# DRIVERS.net
KiCad netlist of a schematic drawn in Altium Designer
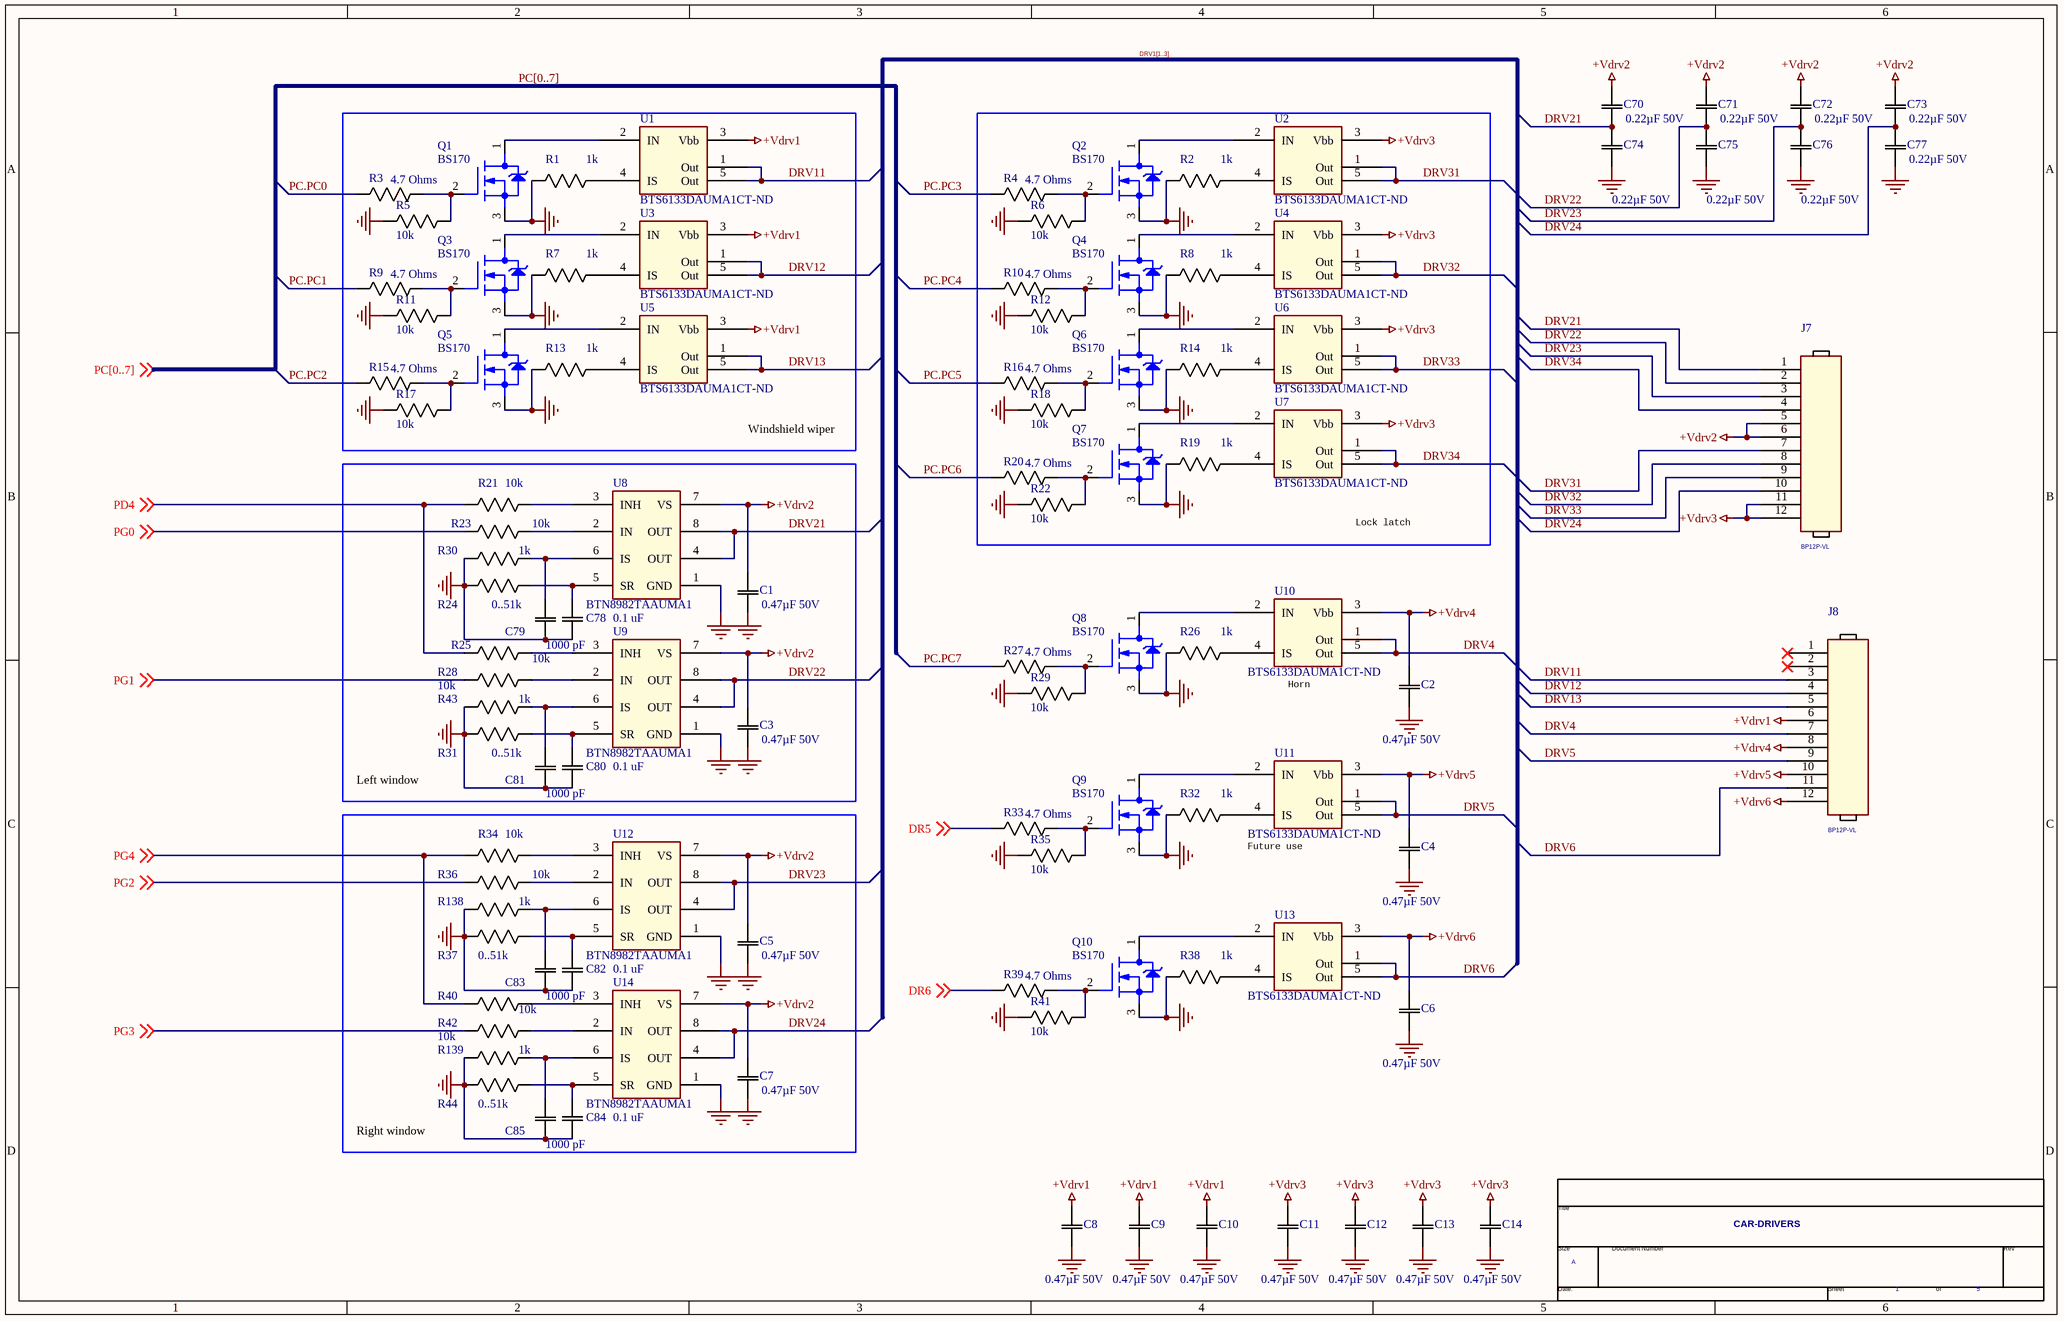
[diagram p0: DRIVERS.SchDoc]

(export (version "E")
  (design (tool "Eeschema 10.0.6"))
  (components
    (comp (ref "C1")
      (value "0.47µF 50V")
      (footprint "SR20")
      (description "CAP CER 0.47UF 50V X7R RADIAL")
      (fields (field (name "MANUFACTURER_PART_NUMBER") "C315C474K5R5TA7303"))
      (libsource (lib "Discrete") (part "CAP RADIAL 2.54"))
    )
    (comp (ref "C2")
      (value "0.47µF 50V")
      (footprint "SR20")
      (description "CAP CER 0.47UF 50V X7R RADIAL")
      (fields (field (name "MANUFACTURER_PART_NUMBER") "C315C474K5R5TA7303"))
      (libsource (lib "Discrete") (part "CAP RADIAL 2.54"))
    )
    (comp (ref "C3")
      (value "0.47µF 50V")
      (footprint "SR20")
      (description "CAP CER 0.47UF 50V X7R RADIAL")
      (fields (field (name "MANUFACTURER_PART_NUMBER") "C315C474K5R5TA7303"))
      (libsource (lib "Discrete") (part "CAP RADIAL 2.54"))
    )
    (comp (ref "C4")
      (value "0.47µF 50V")
      (footprint "SR20")
      (description "CAP CER 0.47UF 50V X7R RADIAL")
      (fields (field (name "MANUFACTURER_PART_NUMBER") "C315C474K5R5TA7303"))
      (libsource (lib "Discrete") (part "CAP RADIAL 2.54"))
    )
    (comp (ref "C5")
      (value "0.47µF 50V")
      (footprint "SR20")
      (description "CAP CER 0.47UF 50V X7R RADIAL")
      (fields (field (name "MANUFACTURER_PART_NUMBER") "C315C474K5R5TA7303"))
      (libsource (lib "Discrete") (part "CAP RADIAL 2.54"))
    )
    (comp (ref "C6")
      (value "0.47µF 50V")
      (footprint "SR20")
      (description "CAP CER 0.47UF 50V X7R RADIAL")
      (fields (field (name "MANUFACTURER_PART_NUMBER") "C315C474K5R5TA7303"))
      (libsource (lib "Discrete") (part "CAP RADIAL 2.54"))
    )
    (comp (ref "C7")
      (value "0.47µF 50V")
      (footprint "SR20")
      (description "CAP CER 0.47UF 50V X7R RADIAL")
      (fields (field (name "MANUFACTURER_PART_NUMBER") "C315C474K5R5TA7303"))
      (libsource (lib "Discrete") (part "CAP RADIAL 2.54"))
    )
    (comp (ref "C8")
      (value "0.47µF 50V")
      (footprint "SR20")
      (description "CAP CER 0.47UF 50V X7R RADIAL")
      (fields (field (name "MANUFACTURER_PART_NUMBER") "C315C474K5R5TA7303"))
      (libsource (lib "Discrete") (part "CAP RADIAL 2.54"))
    )
    (comp (ref "C9")
      (value "0.47µF 50V")
      (footprint "SR20")
      (description "CAP CER 0.47UF 50V X7R RADIAL")
      (fields (field (name "MANUFACTURER_PART_NUMBER") "C315C474K5R5TA7303"))
      (libsource (lib "Discrete") (part "CAP RADIAL 2.54"))
    )
    (comp (ref "C10")
      (value "0.47µF 50V")
      (footprint "SR20")
      (description "CAP CER 0.47UF 50V X7R RADIAL")
      (fields (field (name "MANUFACTURER_PART_NUMBER") "C315C474K5R5TA7303"))
      (libsource (lib "Discrete") (part "CAP RADIAL 2.54"))
    )
    (comp (ref "C11")
      (value "0.47µF 50V")
      (footprint "SR20")
      (description "CAP CER 0.47UF 50V X7R RADIAL")
      (fields (field (name "MANUFACTURER_PART_NUMBER") "C315C474K5R5TA7303"))
      (libsource (lib "Discrete") (part "CAP RADIAL 2.54"))
    )
    (comp (ref "C12")
      (value "0.47µF 50V")
      (footprint "SR20")
      (description "CAP CER 0.47UF 50V X7R RADIAL")
      (fields (field (name "MANUFACTURER_PART_NUMBER") "C315C474K5R5TA7303"))
      (libsource (lib "Discrete") (part "CAP RADIAL 2.54"))
    )
    (comp (ref "C13")
      (value "0.47µF 50V")
      (footprint "SR20")
      (description "CAP CER 0.47UF 50V X7R RADIAL")
      (fields (field (name "MANUFACTURER_PART_NUMBER") "C315C474K5R5TA7303"))
      (libsource (lib "Discrete") (part "CAP RADIAL 2.54"))
    )
    (comp (ref "C14")
      (value "0.47µF 50V")
      (footprint "SR20")
      (description "CAP CER 0.47UF 50V X7R RADIAL")
      (fields (field (name "MANUFACTURER_PART_NUMBER") "C315C474K5R5TA7303"))
      (libsource (lib "Discrete") (part "CAP RADIAL 2.54"))
    )
    (comp (ref "C70")
      (value "0.22µF 50V")
      (footprint "SR20")
      (description "CAP CER 0.22UF 50V X7R RADIAL")
      (fields (field (name "MANUFACTURER_PART_NUMBER") "C320C224K5R5TA"))
      (libsource (lib "Discrete") (part "CAP RADIAL 2.54"))
    )
    (comp (ref "C71")
      (value "0.22µF 50V")
      (footprint "SR20")
      (description "CAP CER 0.22UF 50V X7R RADIAL")
      (fields (field (name "MANUFACTURER_PART_NUMBER") "C320C224K5R5TA"))
      (libsource (lib "Discrete") (part "CAP RADIAL 2.54"))
    )
    (comp (ref "C72")
      (value "0.22µF 50V")
      (footprint "SR20")
      (description "CAP CER 0.22UF 50V X7R RADIAL")
      (fields (field (name "MANUFACTURER_PART_NUMBER") "C320C224K5R5TA"))
      (libsource (lib "Discrete") (part "CAP RADIAL 2.54"))
    )
    (comp (ref "C73")
      (value "0.22µF 50V")
      (footprint "SR20")
      (description "CAP CER 0.22UF 50V X7R RADIAL")
      (fields (field (name "MANUFACTURER_PART_NUMBER") "C320C224K5R5TA"))
      (libsource (lib "Discrete") (part "CAP RADIAL 2.54"))
    )
    (comp (ref "C74")
      (value "0.22µF 50V")
      (footprint "SR20")
      (description "CAP CER 0.22UF 50V X7R RADIAL")
      (fields (field (name "MANUFACTURER_PART_NUMBER") "C320C224K5R5TA"))
      (libsource (lib "Discrete") (part "CAP RADIAL 2.54"))
    )
    (comp (ref "C75")
      (value "0.22µF 50V")
      (footprint "SR20")
      (description "CAP CER 0.22UF 50V X7R RADIAL")
      (fields (field (name "MANUFACTURER_PART_NUMBER") "C320C224K5R5TA"))
      (libsource (lib "Discrete") (part "CAP RADIAL 2.54"))
    )
    (comp (ref "C76")
      (value "0.22µF 50V")
      (footprint "SR20")
      (description "CAP CER 0.22UF 50V X7R RADIAL")
      (fields (field (name "MANUFACTURER_PART_NUMBER") "C320C224K5R5TA"))
      (libsource (lib "Discrete") (part "CAP RADIAL 2.54"))
    )
    (comp (ref "C77")
      (value "0.22µF 50V")
      (footprint "SR20")
      (description "CAP CER 0.22UF 50V X7R RADIAL")
      (fields (field (name "MANUFACTURER_PART_NUMBER") "C320C224K5R5TA"))
      (libsource (lib "Discrete") (part "CAP RADIAL 2.54"))
    )
    (comp (ref "C78")
      (value "0.1 uF")
      (footprint "SR20")
      (description "0.1µF ±10% 100V Ceramic Capacitor X7R Radial")
      (fields (field (name "MANUFACTURER_PART_NUMBER") "C320C104K1R5TA7301"))
      (libsource (lib "Discrete") (part "CAP RADIAL 2.54"))
    )
    (comp (ref "C79")
      (value "1000 pF")
      (footprint "SR20")
      (description "CAP CER 1000PF 50V X7R RADIAL")
      (fields (field (name "MANUFACTURER_PART_NUMBER") "C315C102K5R5TA7301"))
      (libsource (lib "Discrete") (part "CAP RADIAL 2.54"))
    )
    (comp (ref "C80")
      (value "0.1 uF")
      (footprint "SR20")
      (description "0.1µF ±10% 100V Ceramic Capacitor X7R Radial")
      (fields (field (name "MANUFACTURER_PART_NUMBER") "C320C104K1R5TA7301"))
      (libsource (lib "Discrete") (part "CAP RADIAL 2.54"))
    )
    (comp (ref "C81")
      (value "1000 pF")
      (footprint "SR20")
      (description "CAP CER 1000PF 50V X7R RADIAL")
      (fields (field (name "MANUFACTURER_PART_NUMBER") "C315C102K5R5TA7301"))
      (libsource (lib "Discrete") (part "CAP RADIAL 2.54"))
    )
    (comp (ref "C82")
      (value "0.1 uF")
      (footprint "SR20")
      (description "0.1µF ±10% 100V Ceramic Capacitor X7R Radial")
      (fields (field (name "MANUFACTURER_PART_NUMBER") "C320C104K1R5TA7301"))
      (libsource (lib "Discrete") (part "CAP RADIAL 2.54"))
    )
    (comp (ref "C83")
      (value "1000 pF")
      (footprint "SR20")
      (description "CAP CER 1000PF 50V X7R RADIAL")
      (fields (field (name "MANUFACTURER_PART_NUMBER") "C315C102K5R5TA7301"))
      (libsource (lib "Discrete") (part "CAP RADIAL 2.54"))
    )
    (comp (ref "C84")
      (value "0.1 uF")
      (footprint "SR20")
      (description "0.1µF ±10% 100V Ceramic Capacitor X7R Radial")
      (fields (field (name "MANUFACTURER_PART_NUMBER") "C320C104K1R5TA7301"))
      (libsource (lib "Discrete") (part "CAP RADIAL 2.54"))
    )
    (comp (ref "C85")
      (value "1000 pF")
      (footprint "SR20")
      (description "CAP CER 1000PF 50V X7R RADIAL")
      (fields (field (name "MANUFACTURER_PART_NUMBER") "C315C102K5R5TA7301"))
      (libsource (lib "Discrete") (part "CAP RADIAL 2.54"))
    )
    (comp (ref "J7")
      (value "BP12P-VL")
      (footprint "MOLEX_0874271202")
      (libsource (lib "*") (part "HEADER 12"))
    )
    (comp (ref "J8")
      (value "BP12P-VL")
      (footprint "MOLEX_0874271202")
      (libsource (lib "*") (part "HEADER 12"))
    )
    (comp (ref "Q1")
      (value "BS170")
      (footprint "Discrete:TO-92")
      (description "MOSFET N-CH 60V 500MA TO-92")
      (fields (field (name "MANUFACTURER_PART_NUMBER") "ON Semiconductor"))
      (libsource (lib "Discrete") (part "BS170"))
    )
    (comp (ref "Q2")
      (value "BS170")
      (footprint "Discrete:TO-92")
      (description "MOSFET N-CH 60V 500MA TO-92")
      (fields (field (name "MANUFACTURER_PART_NUMBER") "ON Semiconductor"))
      (libsource (lib "Discrete") (part "BS170"))
    )
    (comp (ref "Q3")
      (value "BS170")
      (footprint "Discrete:TO-92")
      (description "MOSFET N-CH 60V 500MA TO-92")
      (fields (field (name "MANUFACTURER_PART_NUMBER") "ON Semiconductor"))
      (libsource (lib "Discrete") (part "BS170"))
    )
    (comp (ref "Q4")
      (value "BS170")
      (footprint "Discrete:TO-92")
      (description "MOSFET N-CH 60V 500MA TO-92")
      (fields (field (name "MANUFACTURER_PART_NUMBER") "ON Semiconductor"))
      (libsource (lib "Discrete") (part "BS170"))
    )
    (comp (ref "Q5")
      (value "BS170")
      (footprint "Discrete:TO-92")
      (description "MOSFET N-CH 60V 500MA TO-92")
      (fields (field (name "MANUFACTURER_PART_NUMBER") "ON Semiconductor"))
      (libsource (lib "Discrete") (part "BS170"))
    )
    (comp (ref "Q6")
      (value "BS170")
      (footprint "Discrete:TO-92")
      (description "MOSFET N-CH 60V 500MA TO-92")
      (fields (field (name "MANUFACTURER_PART_NUMBER") "ON Semiconductor"))
      (libsource (lib "Discrete") (part "BS170"))
    )
    (comp (ref "Q7")
      (value "BS170")
      (footprint "Discrete:TO-92")
      (description "MOSFET N-CH 60V 500MA TO-92")
      (fields (field (name "MANUFACTURER_PART_NUMBER") "ON Semiconductor"))
      (libsource (lib "Discrete") (part "BS170"))
    )
    (comp (ref "Q8")
      (value "BS170")
      (footprint "Discrete:TO-92")
      (description "MOSFET N-CH 60V 500MA TO-92")
      (fields (field (name "MANUFACTURER_PART_NUMBER") "ON Semiconductor"))
      (libsource (lib "Discrete") (part "BS170"))
    )
    (comp (ref "Q9")
      (value "BS170")
      (footprint "Discrete:TO-92")
      (description "MOSFET N-CH 60V 500MA TO-92")
      (fields (field (name "MANUFACTURER_PART_NUMBER") "ON Semiconductor"))
      (libsource (lib "Discrete") (part "BS170"))
    )
    (comp (ref "Q10")
      (value "BS170")
      (footprint "Discrete:TO-92")
      (description "MOSFET N-CH 60V 500MA TO-92")
      (fields (field (name "MANUFACTURER_PART_NUMBER") "ON Semiconductor"))
      (libsource (lib "Discrete") (part "BS170"))
    )
    (comp (ref "R1")
      (value "1k")
      (footprint "RES AXIAL 1/6W")
      (description "RES 1K OHM 1/6W 5% AXIAL")
      (fields (field (name "MANUFACTURER_PART_NUMBER") "CFR-12JB-52-1K"))
      (libsource (lib "Discrete") (part "Resistor Axial  1/6W"))
    )
    (comp (ref "R2")
      (value "1k")
      (footprint "RES AXIAL 1/6W")
      (description "RES 1K OHM 1/6W 5% AXIAL")
      (fields (field (name "MANUFACTURER_PART_NUMBER") "CFR-12JB-52-1K"))
      (libsource (lib "Discrete") (part "Resistor Axial  1/6W"))
    )
    (comp (ref "R3")
      (value "4.7 Ohms")
      (footprint "RES AXIAL 1/6W")
      (description "RES 4.7 OHM 1/6W 5% AXIAL")
      (fields (field (name "MANUFACTURER_PART_NUMBER") "CFR-12JB-52-4R7"))
      (libsource (lib "Discrete") (part "Resistor Axial  1/6W"))
    )
    (comp (ref "R4")
      (value "4.7 Ohms")
      (footprint "RES AXIAL 1/6W")
      (description "RES 4.7 OHM 1/6W 5% AXIAL")
      (fields (field (name "MANUFACTURER_PART_NUMBER") "CFR-12JB-52-4R7"))
      (libsource (lib "Discrete") (part "Resistor Axial  1/6W"))
    )
    (comp (ref "R5")
      (value "10k")
      (footprint "RES AXIAL 1/6W")
      (description "RES 10K OHM 1/6W 5% AXIAL")
      (fields (field (name "MANUFACTURER_PART_NUMBER") "CFR-12JB-52-10K"))
      (libsource (lib "Discrete") (part "Resistor Axial  1/6W"))
    )
    (comp (ref "R6")
      (value "10k")
      (footprint "RES AXIAL 1/6W")
      (description "RES 10K OHM 1/6W 5% AXIAL")
      (fields (field (name "MANUFACTURER_PART_NUMBER") "CFR-12JB-52-10K"))
      (libsource (lib "Discrete") (part "Resistor Axial  1/6W"))
    )
    (comp (ref "R7")
      (value "1k")
      (footprint "RES AXIAL 1/6W")
      (description "RES 1K OHM 1/6W 5% AXIAL")
      (fields (field (name "MANUFACTURER_PART_NUMBER") "CFR-12JB-52-1K"))
      (libsource (lib "Discrete") (part "Resistor Axial  1/6W"))
    )
    (comp (ref "R8")
      (value "1k")
      (footprint "RES AXIAL 1/6W")
      (description "RES 1K OHM 1/6W 5% AXIAL")
      (fields (field (name "MANUFACTURER_PART_NUMBER") "CFR-12JB-52-1K"))
      (libsource (lib "Discrete") (part "Resistor Axial  1/6W"))
    )
    (comp (ref "R9")
      (value "4.7 Ohms")
      (footprint "RES AXIAL 1/6W")
      (description "RES 4.7 OHM 1/6W 5% AXIAL")
      (fields (field (name "MANUFACTURER_PART_NUMBER") "CFR-12JB-52-4R7"))
      (libsource (lib "Discrete") (part "Resistor Axial  1/6W"))
    )
    (comp (ref "R10")
      (value "4.7 Ohms")
      (footprint "RES AXIAL 1/6W")
      (description "RES 4.7 OHM 1/6W 5% AXIAL")
      (fields (field (name "MANUFACTURER_PART_NUMBER") "CFR-12JB-52-4R7"))
      (libsource (lib "Discrete") (part "Resistor Axial  1/6W"))
    )
    (comp (ref "R11")
      (value "10k")
      (footprint "RES AXIAL 1/6W")
      (description "RES 10K OHM 1/6W 5% AXIAL")
      (fields (field (name "MANUFACTURER_PART_NUMBER") "CFR-12JB-52-10K"))
      (libsource (lib "Discrete") (part "Resistor Axial  1/6W"))
    )
    (comp (ref "R12")
      (value "10k")
      (footprint "RES AXIAL 1/6W")
      (description "RES 10K OHM 1/6W 5% AXIAL")
      (fields (field (name "MANUFACTURER_PART_NUMBER") "CFR-12JB-52-10K"))
      (libsource (lib "Discrete") (part "Resistor Axial  1/6W"))
    )
    (comp (ref "R13")
      (value "1k")
      (footprint "RES AXIAL 1/6W")
      (description "RES 1K OHM 1/6W 5% AXIAL")
      (fields (field (name "MANUFACTURER_PART_NUMBER") "CFR-12JB-52-1K"))
      (libsource (lib "Discrete") (part "Resistor Axial  1/6W"))
    )
    (comp (ref "R14")
      (value "1k")
      (footprint "RES AXIAL 1/6W")
      (description "RES 1K OHM 1/6W 5% AXIAL")
      (fields (field (name "MANUFACTURER_PART_NUMBER") "CFR-12JB-52-1K"))
      (libsource (lib "Discrete") (part "Resistor Axial  1/6W"))
    )
    (comp (ref "R15")
      (value "4.7 Ohms")
      (footprint "RES AXIAL 1/6W")
      (description "RES 4.7 OHM 1/6W 5% AXIAL")
      (fields (field (name "MANUFACTURER_PART_NUMBER") "CFR-12JB-52-4R7"))
      (libsource (lib "Discrete") (part "Resistor Axial  1/6W"))
    )
    (comp (ref "R16")
      (value "4.7 Ohms")
      (footprint "RES AXIAL 1/6W")
      (description "RES 4.7 OHM 1/6W 5% AXIAL")
      (fields (field (name "MANUFACTURER_PART_NUMBER") "CFR-12JB-52-4R7"))
      (libsource (lib "Discrete") (part "Resistor Axial  1/6W"))
    )
    (comp (ref "R17")
      (value "10k")
      (footprint "RES AXIAL 1/6W")
      (description "RES 10K OHM 1/6W 5% AXIAL")
      (fields (field (name "MANUFACTURER_PART_NUMBER") "CFR-12JB-52-10K"))
      (libsource (lib "Discrete") (part "Resistor Axial  1/6W"))
    )
    (comp (ref "R18")
      (value "10k")
      (footprint "RES AXIAL 1/6W")
      (description "RES 10K OHM 1/6W 5% AXIAL")
      (fields (field (name "MANUFACTURER_PART_NUMBER") "CFR-12JB-52-10K"))
      (libsource (lib "Discrete") (part "Resistor Axial  1/6W"))
    )
    (comp (ref "R19")
      (value "1k")
      (footprint "RES AXIAL 1/6W")
      (description "RES 1K OHM 1/6W 5% AXIAL")
      (fields (field (name "MANUFACTURER_PART_NUMBER") "CFR-12JB-52-1K"))
      (libsource (lib "Discrete") (part "Resistor Axial  1/6W"))
    )
    (comp (ref "R20")
      (value "4.7 Ohms")
      (footprint "RES AXIAL 1/6W")
      (description "RES 4.7 OHM 1/6W 5% AXIAL")
      (fields (field (name "MANUFACTURER_PART_NUMBER") "CFR-12JB-52-4R7"))
      (libsource (lib "Discrete") (part "Resistor Axial  1/6W"))
    )
    (comp (ref "R21")
      (value "10k")
      (footprint "RES AXIAL 1/6W")
      (description "RES 10K OHM 1/6W 5% AXIAL")
      (fields (field (name "MANUFACTURER_PART_NUMBER") "CFR-12JB-52-10K"))
      (libsource (lib "Discrete") (part "Resistor Axial  1/6W"))
    )
    (comp (ref "R22")
      (value "10k")
      (footprint "RES AXIAL 1/6W")
      (description "RES 10K OHM 1/6W 5% AXIAL")
      (fields (field (name "MANUFACTURER_PART_NUMBER") "CFR-12JB-52-10K"))
      (libsource (lib "Discrete") (part "Resistor Axial  1/6W"))
    )
    (comp (ref "R23")
      (value "10k")
      (footprint "RES AXIAL 1/6W")
      (description "RES 10K OHM 1/6W 5% AXIAL")
      (fields (field (name "MANUFACTURER_PART_NUMBER") "CFR-12JB-52-10K"))
      (libsource (lib "Discrete") (part "Resistor Axial  1/6W"))
    )
    (comp (ref "R24")
      (value "0..51k")
      (footprint "RES AXIAL 1/6W")
      (description "RES 1/6W AXIAL")
      (libsource (lib "Discrete") (part "Resistor Axial  1/6W"))
    )
    (comp (ref "R25")
      (value "10k")
      (footprint "RES AXIAL 1/6W")
      (description "RES 10K OHM 1/6W 5% AXIAL")
      (fields (field (name "MANUFACTURER_PART_NUMBER") "CFR-12JB-52-10K"))
      (libsource (lib "Discrete") (part "Resistor Axial  1/6W"))
    )
    (comp (ref "R26")
      (value "1k")
      (footprint "RES AXIAL 1/6W")
      (description "RES 1K OHM 1/6W 5% AXIAL")
      (fields (field (name "MANUFACTURER_PART_NUMBER") "CFR-12JB-52-1K"))
      (libsource (lib "Discrete") (part "Resistor Axial  1/6W"))
    )
    (comp (ref "R27")
      (value "4.7 Ohms")
      (footprint "RES AXIAL 1/6W")
      (description "RES 4.7 OHM 1/6W 5% AXIAL")
      (fields (field (name "MANUFACTURER_PART_NUMBER") "CFR-12JB-52-4R7"))
      (libsource (lib "Discrete") (part "Resistor Axial  1/6W"))
    )
    (comp (ref "R28")
      (value "10k")
      (footprint "RES AXIAL 1/6W")
      (description "RES 10K OHM 1/6W 5% AXIAL")
      (fields (field (name "MANUFACTURER_PART_NUMBER") "CFR-12JB-52-10K"))
      (libsource (lib "Discrete") (part "Resistor Axial  1/6W"))
    )
    (comp (ref "R29")
      (value "10k")
      (footprint "RES AXIAL 1/6W")
      (description "RES 10K OHM 1/6W 5% AXIAL")
      (fields (field (name "MANUFACTURER_PART_NUMBER") "CFR-12JB-52-10K"))
      (libsource (lib "Discrete") (part "Resistor Axial  1/6W"))
    )
    (comp (ref "R30")
      (value "1k")
      (footprint "RES AXIAL 1/6W")
      (description "RES 1K OHM 1/6W 5% AXIAL")
      (fields (field (name "MANUFACTURER_PART_NUMBER") "CFR-12JB-52-1K"))
      (libsource (lib "Discrete") (part "Resistor Axial  1/6W"))
    )
    (comp (ref "R31")
      (value "0..51k")
      (footprint "RES AXIAL 1/6W")
      (description "RES 1/6W AXIAL")
      (libsource (lib "Discrete") (part "Resistor Axial  1/6W"))
    )
    (comp (ref "R32")
      (value "1k")
      (footprint "RES AXIAL 1/6W")
      (description "RES 1K OHM 1/6W 5% AXIAL")
      (fields (field (name "MANUFACTURER_PART_NUMBER") "CFR-12JB-52-1K"))
      (libsource (lib "Discrete") (part "Resistor Axial  1/6W"))
    )
    (comp (ref "R33")
      (value "4.7 Ohms")
      (footprint "RES AXIAL 1/6W")
      (description "RES 4.7 OHM 1/6W 5% AXIAL")
      (fields (field (name "MANUFACTURER_PART_NUMBER") "CFR-12JB-52-4R7"))
      (libsource (lib "Discrete") (part "Resistor Axial  1/6W"))
    )
    (comp (ref "R34")
      (value "10k")
      (footprint "RES AXIAL 1/6W")
      (description "RES 10K OHM 1/6W 5% AXIAL")
      (fields (field (name "MANUFACTURER_PART_NUMBER") "CFR-12JB-52-10K"))
      (libsource (lib "Discrete") (part "Resistor Axial  1/6W"))
    )
    (comp (ref "R35")
      (value "10k")
      (footprint "RES AXIAL 1/6W")
      (description "RES 10K OHM 1/6W 5% AXIAL")
      (fields (field (name "MANUFACTURER_PART_NUMBER") "CFR-12JB-52-10K"))
      (libsource (lib "Discrete") (part "Resistor Axial  1/6W"))
    )
    (comp (ref "R36")
      (value "10k")
      (footprint "RES AXIAL 1/6W")
      (description "RES 10K OHM 1/6W 5% AXIAL")
      (fields (field (name "MANUFACTURER_PART_NUMBER") "CFR-12JB-52-10K"))
      (libsource (lib "Discrete") (part "Resistor Axial  1/6W"))
    )
    (comp (ref "R37")
      (value "0..51k")
      (footprint "RES AXIAL 1/6W")
      (description "RES 1/6W AXIAL")
      (libsource (lib "Discrete") (part "Resistor Axial  1/6W"))
    )
    (comp (ref "R38")
      (value "1k")
      (footprint "RES AXIAL 1/6W")
      (description "RES 1K OHM 1/6W 5% AXIAL")
      (fields (field (name "MANUFACTURER_PART_NUMBER") "CFR-12JB-52-1K"))
      (libsource (lib "Discrete") (part "Resistor Axial  1/6W"))
    )
    (comp (ref "R39")
      (value "4.7 Ohms")
      (footprint "RES AXIAL 1/6W")
      (description "RES 4.7 OHM 1/6W 5% AXIAL")
      (fields (field (name "MANUFACTURER_PART_NUMBER") "CFR-12JB-52-4R7"))
      (libsource (lib "Discrete") (part "Resistor Axial  1/6W"))
    )
    (comp (ref "R40")
      (value "10k")
      (footprint "RES AXIAL 1/6W")
      (description "RES 10K OHM 1/6W 5% AXIAL")
      (fields (field (name "MANUFACTURER_PART_NUMBER") "CFR-12JB-52-10K"))
      (libsource (lib "Discrete") (part "Resistor Axial  1/6W"))
    )
    (comp (ref "R41")
      (value "10k")
      (footprint "RES AXIAL 1/6W")
      (description "RES 10K OHM 1/6W 5% AXIAL")
      (fields (field (name "MANUFACTURER_PART_NUMBER") "CFR-12JB-52-10K"))
      (libsource (lib "Discrete") (part "Resistor Axial  1/6W"))
    )
    (comp (ref "R42")
      (value "10k")
      (footprint "RES AXIAL 1/6W")
      (description "RES 10K OHM 1/6W 5% AXIAL")
      (fields (field (name "MANUFACTURER_PART_NUMBER") "CFR-12JB-52-10K"))
      (libsource (lib "Discrete") (part "Resistor Axial  1/6W"))
    )
    (comp (ref "R43")
      (value "1k")
      (footprint "RES AXIAL 1/6W")
      (description "RES 1K OHM 1/6W 5% AXIAL")
      (fields (field (name "MANUFACTURER_PART_NUMBER") "CFR-12JB-52-1K"))
      (libsource (lib "Discrete") (part "Resistor Axial  1/6W"))
    )
    (comp (ref "R44")
      (value "0..51k")
      (footprint "RES AXIAL 1/6W")
      (description "RES 1/6W AXIAL")
      (libsource (lib "Discrete") (part "Resistor Axial  1/6W"))
    )
    (comp (ref "R138")
      (value "1k")
      (footprint "RES AXIAL 1/6W")
      (description "RES 1K OHM 1/6W 5% AXIAL")
      (fields (field (name "MANUFACTURER_PART_NUMBER") "CFR-12JB-52-1K"))
      (libsource (lib "Discrete") (part "Resistor Axial  1/6W"))
    )
    (comp (ref "R139")
      (value "1k")
      (footprint "RES AXIAL 1/6W")
      (description "RES 1K OHM 1/6W 5% AXIAL")
      (fields (field (name "MANUFACTURER_PART_NUMBER") "CFR-12JB-52-1K"))
      (libsource (lib "Discrete") (part "Resistor Axial  1/6W"))
    )
    (comp (ref "U1")
      (value "BTS6133DAUMA1CT-ND")
      (footprint "TO114P998X235-6_5N_L")
      (libsource (lib "CAR_Library") (part "BTS6133DAUMA1CT-ND"))
    )
    (comp (ref "U2")
      (value "BTS6133DAUMA1CT-ND")
      (footprint "TO114P998X235-6_5N_L")
      (libsource (lib "CAR_Library") (part "BTS6133DAUMA1CT-ND"))
    )
    (comp (ref "U3")
      (value "BTS6133DAUMA1CT-ND")
      (footprint "TO114P998X235-6_5N_L")
      (libsource (lib "CAR_Library") (part "BTS6133DAUMA1CT-ND"))
    )
    (comp (ref "U4")
      (value "BTS6133DAUMA1CT-ND")
      (footprint "TO114P998X235-6_5N_L")
      (libsource (lib "CAR_Library") (part "BTS6133DAUMA1CT-ND"))
    )
    (comp (ref "U5")
      (value "BTS6133DAUMA1CT-ND")
      (footprint "TO114P998X235-6_5N_L")
      (libsource (lib "CAR_Library") (part "BTS6133DAUMA1CT-ND"))
    )
    (comp (ref "U6")
      (value "BTS6133DAUMA1CT-ND")
      (footprint "TO114P998X235-6_5N_L")
      (libsource (lib "CAR_Library") (part "BTS6133DAUMA1CT-ND"))
    )
    (comp (ref "U7")
      (value "BTS6133DAUMA1CT-ND")
      (footprint "TO114P998X235-6_5N_L")
      (libsource (lib "CAR_Library") (part "BTS6133DAUMA1CT-ND"))
    )
    (comp (ref "U8") (value "BTN8982TAAUMA1") (footprint "TO263-7") (libsource (lib "*") (part "BTN7971B")))
    (comp (ref "U9") (value "BTN8982TAAUMA1") (footprint "TO263-7") (libsource (lib "*") (part "BTN7971B")))
    (comp (ref "U10")
      (value "BTS6133DAUMA1CT-ND")
      (footprint "TO114P998X235-6_5N_L")
      (libsource (lib "CAR_Library") (part "BTS6133DAUMA1CT-ND"))
    )
    (comp (ref "U11")
      (value "BTS6133DAUMA1CT-ND")
      (footprint "TO114P998X235-6_5N_L")
      (libsource (lib "CAR_Library") (part "BTS6133DAUMA1CT-ND"))
    )
    (comp (ref "U12") (value "BTN8982TAAUMA1") (footprint "TO263-7") (libsource (lib "*") (part "BTN7971B")))
    (comp (ref "U13")
      (value "BTS6133DAUMA1CT-ND")
      (footprint "TO114P998X235-6_5N_L")
      (libsource (lib "CAR_Library") (part "BTS6133DAUMA1CT-ND"))
    )
    (comp (ref "U14") (value "BTN8982TAAUMA1") (footprint "TO263-7") (libsource (lib "*") (part "BTN7971B")))
  )
  (nets
    (net (code "1") (name "+Vdrv1") (class "Default")
      (node (ref "C10") (pin "2") (pinfunction "2_2") (pintype "passive"))
      (node (ref "C8") (pin "2") (pinfunction "2_2") (pintype "passive"))
      (node (ref "C9") (pin "2") (pinfunction "2_2") (pintype "passive"))
      (node (ref "J8") (pin "6") (pinfunction "6_6") (pintype "passive"))
      (node (ref "U1") (pin "3") (pinfunction "Vbb_3") (pintype "passive"))
      (node (ref "U3") (pin "3") (pinfunction "Vbb_3") (pintype "passive"))
      (node (ref "U5") (pin "3") (pinfunction "Vbb_3") (pintype "passive"))
    )
    (net (code "2") (name "+Vdrv2") (class "Default")
      (node (ref "C1") (pin "2") (pinfunction "2_2") (pintype "passive"))
      (node (ref "C3") (pin "2") (pinfunction "2_2") (pintype "passive"))
      (node (ref "C5") (pin "2") (pinfunction "2_2") (pintype "passive"))
      (node (ref "C7") (pin "2") (pinfunction "2_2") (pintype "passive"))
      (node (ref "C70") (pin "2") (pinfunction "2_2") (pintype "passive"))
      (node (ref "C71") (pin "2") (pinfunction "2_2") (pintype "passive"))
      (node (ref "C72") (pin "2") (pinfunction "2_2") (pintype "passive"))
      (node (ref "C73") (pin "2") (pinfunction "2_2") (pintype "passive"))
      (node (ref "J7") (pin "5") (pinfunction "5_5") (pintype "passive"))
      (node (ref "J7") (pin "6") (pinfunction "6_6") (pintype "passive"))
      (node (ref "U12") (pin "7") (pinfunction "VS_7") (pintype "passive"))
      (node (ref "U14") (pin "7") (pinfunction "VS_7") (pintype "passive"))
      (node (ref "U8") (pin "7") (pinfunction "VS_7") (pintype "passive"))
      (node (ref "U9") (pin "7") (pinfunction "VS_7") (pintype "passive"))
    )
    (net (code "3") (name "+Vdrv3") (class "Default")
      (node (ref "C11") (pin "2") (pinfunction "2_2") (pintype "passive"))
      (node (ref "C12") (pin "2") (pinfunction "2_2") (pintype "passive"))
      (node (ref "C13") (pin "2") (pinfunction "2_2") (pintype "passive"))
      (node (ref "C14") (pin "2") (pinfunction "2_2") (pintype "passive"))
      (node (ref "J7") (pin "11") (pinfunction "11_11") (pintype "passive"))
      (node (ref "J7") (pin "12") (pinfunction "12_12") (pintype "passive"))
      (node (ref "U2") (pin "3") (pinfunction "Vbb_3") (pintype "passive"))
      (node (ref "U4") (pin "3") (pinfunction "Vbb_3") (pintype "passive"))
      (node (ref "U6") (pin "3") (pinfunction "Vbb_3") (pintype "passive"))
      (node (ref "U7") (pin "3") (pinfunction "Vbb_3") (pintype "passive"))
    )
    (net (code "4") (name "+Vdrv4") (class "Default")
      (node (ref "C2") (pin "2") (pinfunction "2_2") (pintype "passive"))
      (node (ref "J8") (pin "8") (pinfunction "8_8") (pintype "passive"))
      (node (ref "U10") (pin "3") (pinfunction "Vbb_3") (pintype "passive"))
    )
    (net (code "5") (name "+Vdrv5") (class "Default")
      (node (ref "C4") (pin "2") (pinfunction "2_2") (pintype "passive"))
      (node (ref "J8") (pin "10") (pinfunction "10_10") (pintype "passive"))
      (node (ref "U11") (pin "3") (pinfunction "Vbb_3") (pintype "passive"))
    )
    (net (code "6") (name "+Vdrv6") (class "Default")
      (node (ref "C6") (pin "2") (pinfunction "2_2") (pintype "passive"))
      (node (ref "J8") (pin "12") (pinfunction "12_12") (pintype "passive"))
      (node (ref "U13") (pin "3") (pinfunction "Vbb_3") (pintype "passive"))
    )
    (net (code "8") (name "/DRV4") (class "Default")
      (node (ref "J8") (pin "7") (pinfunction "7_7") (pintype "passive"))
      (node (ref "U10") (pin "1") (pinfunction "Out_1") (pintype "passive"))
      (node (ref "U10") (pin "5") (pinfunction "Out_5") (pintype "passive"))
    )
    (net (code "9") (name "/DRV5") (class "Default")
      (node (ref "J8") (pin "9") (pinfunction "9_9") (pintype "passive"))
      (node (ref "U11") (pin "1") (pinfunction "Out_1") (pintype "passive"))
      (node (ref "U11") (pin "5") (pinfunction "Out_5") (pintype "passive"))
    )
    (net (code "10") (name "/DRV6") (class "Default")
      (node (ref "J8") (pin "11") (pinfunction "11_11") (pintype "passive"))
      (node (ref "U13") (pin "1") (pinfunction "Out_1") (pintype "passive"))
      (node (ref "U13") (pin "5") (pinfunction "Out_5") (pintype "passive"))
    )
    (net (code "11") (name "/DRV11") (class "Default")
      (node (ref "J8") (pin "3") (pinfunction "3_3") (pintype "passive"))
      (node (ref "U1") (pin "1") (pinfunction "Out_1") (pintype "passive"))
      (node (ref "U1") (pin "5") (pinfunction "Out_5") (pintype "passive"))
    )
    (net (code "12") (name "/DRV12") (class "Default")
      (node (ref "J8") (pin "4") (pinfunction "4_4") (pintype "passive"))
      (node (ref "U3") (pin "1") (pinfunction "Out_1") (pintype "passive"))
      (node (ref "U3") (pin "5") (pinfunction "Out_5") (pintype "passive"))
    )
    (net (code "13") (name "/DRV13") (class "Default")
      (node (ref "J8") (pin "5") (pinfunction "5_5") (pintype "passive"))
      (node (ref "U5") (pin "1") (pinfunction "Out_1") (pintype "passive"))
      (node (ref "U5") (pin "5") (pinfunction "Out_5") (pintype "passive"))
    )
    (net (code "14") (name "/DRV21") (class "Default")
      (node (ref "C70") (pin "1") (pinfunction "1_1") (pintype "passive"))
      (node (ref "C74") (pin "2") (pinfunction "2_2") (pintype "passive"))
      (node (ref "J7") (pin "1") (pinfunction "1_1") (pintype "passive"))
      (node (ref "U8") (pin "4") (pinfunction "OUT_4") (pintype "passive"))
      (node (ref "U8") (pin "8") (pinfunction "OUT_8") (pintype "passive"))
    )
    (net (code "15") (name "/DRV22") (class "Default")
      (node (ref "C71") (pin "1") (pinfunction "1_1") (pintype "passive"))
      (node (ref "C75") (pin "2") (pinfunction "2_2") (pintype "passive"))
      (node (ref "J7") (pin "2") (pinfunction "2_2") (pintype "passive"))
      (node (ref "U9") (pin "4") (pinfunction "OUT_4") (pintype "passive"))
      (node (ref "U9") (pin "8") (pinfunction "OUT_8") (pintype "passive"))
    )
    (net (code "16") (name "/DRV23") (class "Default")
      (node (ref "C72") (pin "1") (pinfunction "1_1") (pintype "passive"))
      (node (ref "C76") (pin "2") (pinfunction "2_2") (pintype "passive"))
      (node (ref "J7") (pin "3") (pinfunction "3_3") (pintype "passive"))
      (node (ref "U12") (pin "4") (pinfunction "OUT_4") (pintype "passive"))
      (node (ref "U12") (pin "8") (pinfunction "OUT_8") (pintype "passive"))
    )
    (net (code "17") (name "/DRV24") (class "Default")
      (node (ref "C73") (pin "1") (pinfunction "1_1") (pintype "passive"))
      (node (ref "C77") (pin "2") (pinfunction "2_2") (pintype "passive"))
      (node (ref "J7") (pin "10") (pinfunction "10_10") (pintype "passive"))
      (node (ref "U14") (pin "4") (pinfunction "OUT_4") (pintype "passive"))
      (node (ref "U14") (pin "8") (pinfunction "OUT_8") (pintype "passive"))
    )
    (net (code "18") (name "/DRV31") (class "Default")
      (node (ref "J7") (pin "7") (pinfunction "7_7") (pintype "passive"))
      (node (ref "U2") (pin "1") (pinfunction "Out_1") (pintype "passive"))
      (node (ref "U2") (pin "5") (pinfunction "Out_5") (pintype "passive"))
    )
    (net (code "19") (name "/DRV32") (class "Default")
      (node (ref "J7") (pin "8") (pinfunction "8_8") (pintype "passive"))
      (node (ref "U4") (pin "1") (pinfunction "Out_1") (pintype "passive"))
      (node (ref "U4") (pin "5") (pinfunction "Out_5") (pintype "passive"))
    )
    (net (code "20") (name "/DRV33") (class "Default")
      (node (ref "J7") (pin "9") (pinfunction "9_9") (pintype "passive"))
      (node (ref "U6") (pin "1") (pinfunction "Out_1") (pintype "passive"))
      (node (ref "U6") (pin "5") (pinfunction "Out_5") (pintype "passive"))
    )
    (net (code "21") (name "/DRV34") (class "Default")
      (node (ref "J7") (pin "4") (pinfunction "4_4") (pintype "passive"))
      (node (ref "U7") (pin "1") (pinfunction "Out_1") (pintype "passive"))
      (node (ref "U7") (pin "5") (pinfunction "Out_5") (pintype "passive"))
    )
    (net (code "22") (name "/PC.PC0") (class "Default")
      (node (ref "R3") (pin "2") (pinfunction "2_2") (pintype "passive"))
    )
    (net (code "23") (name "/PC.PC1") (class "Default")
      (node (ref "R9") (pin "2") (pinfunction "2_2") (pintype "passive"))
    )
    (net (code "24") (name "/PC.PC2") (class "Default")
      (node (ref "R15") (pin "2") (pinfunction "2_2") (pintype "passive"))
    )
    (net (code "25") (name "/PC.PC3") (class "Default")
      (node (ref "R4") (pin "2") (pinfunction "2_2") (pintype "passive"))
    )
    (net (code "26") (name "/PC.PC4") (class "Default")
      (node (ref "R10") (pin "2") (pinfunction "2_2") (pintype "passive"))
    )
    (net (code "27") (name "/PC.PC5") (class "Default")
      (node (ref "R16") (pin "2") (pinfunction "2_2") (pintype "passive"))
    )
    (net (code "28") (name "/PC.PC6") (class "Default")
      (node (ref "R20") (pin "2") (pinfunction "2_2") (pintype "passive"))
    )
    (net (code "29") (name "/PC.PC7") (class "Default")
      (node (ref "R27") (pin "2") (pinfunction "2_2") (pintype "passive"))
    )
    (net (code "30") (name "DR5") (class "Default")
      (node (ref "R33") (pin "2") (pinfunction "2_2") (pintype "passive"))
    )
    (net (code "31") (name "DR6") (class "Default")
      (node (ref "R39") (pin "2") (pinfunction "2_2") (pintype "passive"))
    )
    (net (code "32") (name "GND") (class "Default")
      (node (ref "C1") (pin "1") (pinfunction "1_1") (pintype "passive"))
      (node (ref "C10") (pin "1") (pinfunction "1_1") (pintype "passive"))
      (node (ref "C11") (pin "1") (pinfunction "1_1") (pintype "passive"))
      (node (ref "C12") (pin "1") (pinfunction "1_1") (pintype "passive"))
      (node (ref "C13") (pin "1") (pinfunction "1_1") (pintype "passive"))
      (node (ref "C14") (pin "1") (pinfunction "1_1") (pintype "passive"))
      (node (ref "C2") (pin "1") (pinfunction "1_1") (pintype "passive"))
      (node (ref "C3") (pin "1") (pinfunction "1_1") (pintype "passive"))
      (node (ref "C4") (pin "1") (pinfunction "1_1") (pintype "passive"))
      (node (ref "C5") (pin "1") (pinfunction "1_1") (pintype "passive"))
      (node (ref "C6") (pin "1") (pinfunction "1_1") (pintype "passive"))
      (node (ref "C7") (pin "1") (pinfunction "1_1") (pintype "passive"))
      (node (ref "C74") (pin "1") (pinfunction "1_1") (pintype "passive"))
      (node (ref "C75") (pin "1") (pinfunction "1_1") (pintype "passive"))
      (node (ref "C76") (pin "1") (pinfunction "1_1") (pintype "passive"))
      (node (ref "C77") (pin "1") (pinfunction "1_1") (pintype "passive"))
      (node (ref "C78") (pin "2") (pinfunction "2_2") (pintype "passive"))
      (node (ref "C79") (pin "1") (pinfunction "1_1") (pintype "passive"))
      (node (ref "C8") (pin "1") (pinfunction "1_1") (pintype "passive"))
      (node (ref "C80") (pin "2") (pinfunction "2_2") (pintype "passive"))
      (node (ref "C81") (pin "1") (pinfunction "1_1") (pintype "passive"))
      (node (ref "C82") (pin "2") (pinfunction "2_2") (pintype "passive"))
      (node (ref "C83") (pin "1") (pinfunction "1_1") (pintype "passive"))
      (node (ref "C84") (pin "2") (pinfunction "2_2") (pintype "passive"))
      (node (ref "C85") (pin "1") (pinfunction "1_1") (pintype "passive"))
      (node (ref "C9") (pin "1") (pinfunction "1_1") (pintype "passive"))
      (node (ref "Q1") (pin "3") (pinfunction "S_3") (pintype "passive"))
      (node (ref "Q10") (pin "3") (pinfunction "S_3") (pintype "passive"))
      (node (ref "Q2") (pin "3") (pinfunction "S_3") (pintype "passive"))
      (node (ref "Q3") (pin "3") (pinfunction "S_3") (pintype "passive"))
      (node (ref "Q4") (pin "3") (pinfunction "S_3") (pintype "passive"))
      (node (ref "Q5") (pin "3") (pinfunction "S_3") (pintype "passive"))
      (node (ref "Q6") (pin "3") (pinfunction "S_3") (pintype "passive"))
      (node (ref "Q7") (pin "3") (pinfunction "S_3") (pintype "passive"))
      (node (ref "Q8") (pin "3") (pinfunction "S_3") (pintype "passive"))
      (node (ref "Q9") (pin "3") (pinfunction "S_3") (pintype "passive"))
      (node (ref "R1") (pin "2") (pinfunction "2_2") (pintype "passive"))
      (node (ref "R11") (pin "1") (pinfunction "1_1") (pintype "passive"))
      (node (ref "R12") (pin "1") (pinfunction "1_1") (pintype "passive"))
      (node (ref "R13") (pin "2") (pinfunction "2_2") (pintype "passive"))
      (node (ref "R138") (pin "2") (pinfunction "2_2") (pintype "passive"))
      (node (ref "R139") (pin "2") (pinfunction "2_2") (pintype "passive"))
      (node (ref "R14") (pin "2") (pinfunction "2_2") (pintype "passive"))
      (node (ref "R17") (pin "1") (pinfunction "1_1") (pintype "passive"))
      (node (ref "R18") (pin "1") (pinfunction "1_1") (pintype "passive"))
      (node (ref "R19") (pin "2") (pinfunction "2_2") (pintype "passive"))
      (node (ref "R2") (pin "2") (pinfunction "2_2") (pintype "passive"))
      (node (ref "R22") (pin "1") (pinfunction "1_1") (pintype "passive"))
      (node (ref "R24") (pin "1") (pinfunction "1_1") (pintype "passive"))
      (node (ref "R26") (pin "2") (pinfunction "2_2") (pintype "passive"))
      (node (ref "R29") (pin "1") (pinfunction "1_1") (pintype "passive"))
      (node (ref "R30") (pin "2") (pinfunction "2_2") (pintype "passive"))
      (node (ref "R31") (pin "1") (pinfunction "1_1") (pintype "passive"))
      (node (ref "R32") (pin "2") (pinfunction "2_2") (pintype "passive"))
      (node (ref "R35") (pin "1") (pinfunction "1_1") (pintype "passive"))
      (node (ref "R37") (pin "1") (pinfunction "1_1") (pintype "passive"))
      (node (ref "R38") (pin "2") (pinfunction "2_2") (pintype "passive"))
      (node (ref "R41") (pin "1") (pinfunction "1_1") (pintype "passive"))
      (node (ref "R43") (pin "2") (pinfunction "2_2") (pintype "passive"))
      (node (ref "R44") (pin "1") (pinfunction "1_1") (pintype "passive"))
      (node (ref "R5") (pin "1") (pinfunction "1_1") (pintype "passive"))
      (node (ref "R6") (pin "1") (pinfunction "1_1") (pintype "passive"))
      (node (ref "R7") (pin "2") (pinfunction "2_2") (pintype "passive"))
      (node (ref "R8") (pin "2") (pinfunction "2_2") (pintype "passive"))
      (node (ref "U12") (pin "1") (pinfunction "GND_1") (pintype "passive"))
      (node (ref "U14") (pin "1") (pinfunction "GND_1") (pintype "passive"))
      (node (ref "U8") (pin "1") (pinfunction "GND_1") (pintype "passive"))
      (node (ref "U9") (pin "1") (pinfunction "GND_1") (pintype "passive"))
    )
    (net (code "33") (name "Net-(Q1-D)") (class "Default")
      (node (ref "Q1") (pin "1") (pinfunction "D_1") (pintype "passive"))
      (node (ref "U1") (pin "2") (pinfunction "IN_2") (pintype "passive"))
    )
    (net (code "34") (name "Net-(Q1-G)") (class "Default")
      (node (ref "Q1") (pin "2") (pinfunction "G_2") (pintype "passive"))
      (node (ref "R3") (pin "1") (pinfunction "1_1") (pintype "passive"))
      (node (ref "R5") (pin "2") (pinfunction "2_2") (pintype "passive"))
    )
    (net (code "35") (name "Net-(Q2-D)") (class "Default")
      (node (ref "Q2") (pin "1") (pinfunction "D_1") (pintype "passive"))
      (node (ref "U2") (pin "2") (pinfunction "IN_2") (pintype "passive"))
    )
    (net (code "36") (name "Net-(Q2-G)") (class "Default")
      (node (ref "Q2") (pin "2") (pinfunction "G_2") (pintype "passive"))
      (node (ref "R4") (pin "1") (pinfunction "1_1") (pintype "passive"))
      (node (ref "R6") (pin "2") (pinfunction "2_2") (pintype "passive"))
    )
    (net (code "37") (name "Net-(Q3-D)") (class "Default")
      (node (ref "Q3") (pin "1") (pinfunction "D_1") (pintype "passive"))
      (node (ref "U3") (pin "2") (pinfunction "IN_2") (pintype "passive"))
    )
    (net (code "38") (name "Net-(Q3-G)") (class "Default")
      (node (ref "Q3") (pin "2") (pinfunction "G_2") (pintype "passive"))
      (node (ref "R11") (pin "2") (pinfunction "2_2") (pintype "passive"))
      (node (ref "R9") (pin "1") (pinfunction "1_1") (pintype "passive"))
    )
    (net (code "39") (name "Net-(Q4-D)") (class "Default")
      (node (ref "Q4") (pin "1") (pinfunction "D_1") (pintype "passive"))
      (node (ref "U4") (pin "2") (pinfunction "IN_2") (pintype "passive"))
    )
    (net (code "40") (name "Net-(Q4-G)") (class "Default")
      (node (ref "Q4") (pin "2") (pinfunction "G_2") (pintype "passive"))
      (node (ref "R10") (pin "1") (pinfunction "1_1") (pintype "passive"))
      (node (ref "R12") (pin "2") (pinfunction "2_2") (pintype "passive"))
    )
    (net (code "41") (name "Net-(Q5-D)") (class "Default")
      (node (ref "Q5") (pin "1") (pinfunction "D_1") (pintype "passive"))
      (node (ref "U5") (pin "2") (pinfunction "IN_2") (pintype "passive"))
    )
    (net (code "42") (name "Net-(Q5-G)") (class "Default")
      (node (ref "Q5") (pin "2") (pinfunction "G_2") (pintype "passive"))
      (node (ref "R15") (pin "1") (pinfunction "1_1") (pintype "passive"))
      (node (ref "R17") (pin "2") (pinfunction "2_2") (pintype "passive"))
    )
    (net (code "43") (name "Net-(Q6-D)") (class "Default")
      (node (ref "Q6") (pin "1") (pinfunction "D_1") (pintype "passive"))
      (node (ref "U6") (pin "2") (pinfunction "IN_2") (pintype "passive"))
    )
    (net (code "44") (name "Net-(Q6-G)") (class "Default")
      (node (ref "Q6") (pin "2") (pinfunction "G_2") (pintype "passive"))
      (node (ref "R16") (pin "1") (pinfunction "1_1") (pintype "passive"))
      (node (ref "R18") (pin "2") (pinfunction "2_2") (pintype "passive"))
    )
    (net (code "45") (name "Net-(Q7-D)") (class "Default")
      (node (ref "Q7") (pin "1") (pinfunction "D_1") (pintype "passive"))
      (node (ref "U7") (pin "2") (pinfunction "IN_2") (pintype "passive"))
    )
    (net (code "46") (name "Net-(Q7-G)") (class "Default")
      (node (ref "Q7") (pin "2") (pinfunction "G_2") (pintype "passive"))
      (node (ref "R20") (pin "1") (pinfunction "1_1") (pintype "passive"))
      (node (ref "R22") (pin "2") (pinfunction "2_2") (pintype "passive"))
    )
    (net (code "47") (name "Net-(Q8-D)") (class "Default")
      (node (ref "Q8") (pin "1") (pinfunction "D_1") (pintype "passive"))
      (node (ref "U10") (pin "2") (pinfunction "IN_2") (pintype "passive"))
    )
    (net (code "48") (name "Net-(Q8-G)") (class "Default")
      (node (ref "Q8") (pin "2") (pinfunction "G_2") (pintype "passive"))
      (node (ref "R27") (pin "1") (pinfunction "1_1") (pintype "passive"))
      (node (ref "R29") (pin "2") (pinfunction "2_2") (pintype "passive"))
    )
    (net (code "49") (name "Net-(Q9-D)") (class "Default")
      (node (ref "Q9") (pin "1") (pinfunction "D_1") (pintype "passive"))
      (node (ref "U11") (pin "2") (pinfunction "IN_2") (pintype "passive"))
    )
    (net (code "50") (name "Net-(Q9-G)") (class "Default")
      (node (ref "Q9") (pin "2") (pinfunction "G_2") (pintype "passive"))
      (node (ref "R33") (pin "1") (pinfunction "1_1") (pintype "passive"))
      (node (ref "R35") (pin "2") (pinfunction "2_2") (pintype "passive"))
    )
    (net (code "51") (name "Net-(Q10-D)") (class "Default")
      (node (ref "Q10") (pin "1") (pinfunction "D_1") (pintype "passive"))
      (node (ref "U13") (pin "2") (pinfunction "IN_2") (pintype "passive"))
    )
    (net (code "52") (name "Net-(Q10-G)") (class "Default")
      (node (ref "Q10") (pin "2") (pinfunction "G_2") (pintype "passive"))
      (node (ref "R39") (pin "1") (pinfunction "1_1") (pintype "passive"))
      (node (ref "R41") (pin "2") (pinfunction "2_2") (pintype "passive"))
    )
    (net (code "53") (name "Net-(U1-IS)") (class "Default")
      (node (ref "R1") (pin "1") (pinfunction "1_1") (pintype "passive"))
      (node (ref "U1") (pin "4") (pinfunction "IS_4") (pintype "passive"))
    )
    (net (code "54") (name "Net-(U2-IS)") (class "Default")
      (node (ref "R2") (pin "1") (pinfunction "1_1") (pintype "passive"))
      (node (ref "U2") (pin "4") (pinfunction "IS_4") (pintype "passive"))
    )
    (net (code "55") (name "Net-(U3-IS)") (class "Default")
      (node (ref "R7") (pin "1") (pinfunction "1_1") (pintype "passive"))
      (node (ref "U3") (pin "4") (pinfunction "IS_4") (pintype "passive"))
    )
    (net (code "56") (name "Net-(U4-IS)") (class "Default")
      (node (ref "R8") (pin "1") (pinfunction "1_1") (pintype "passive"))
      (node (ref "U4") (pin "4") (pinfunction "IS_4") (pintype "passive"))
    )
    (net (code "57") (name "Net-(U5-IS)") (class "Default")
      (node (ref "R13") (pin "1") (pinfunction "1_1") (pintype "passive"))
      (node (ref "U5") (pin "4") (pinfunction "IS_4") (pintype "passive"))
    )
    (net (code "58") (name "Net-(U6-IS)") (class "Default")
      (node (ref "R14") (pin "1") (pinfunction "1_1") (pintype "passive"))
      (node (ref "U6") (pin "4") (pinfunction "IS_4") (pintype "passive"))
    )
    (net (code "59") (name "Net-(U7-IS)") (class "Default")
      (node (ref "R19") (pin "1") (pinfunction "1_1") (pintype "passive"))
      (node (ref "U7") (pin "4") (pinfunction "IS_4") (pintype "passive"))
    )
    (net (code "60") (name "Net-(U8-IN)") (class "Default")
      (node (ref "R23") (pin "2") (pinfunction "2_2") (pintype "passive"))
      (node (ref "U8") (pin "2") (pinfunction "IN_2") (pintype "passive"))
    )
    (net (code "61") (name "Net-(U8-INH)") (class "Default")
      (node (ref "R21") (pin "2") (pinfunction "2_2") (pintype "passive"))
      (node (ref "U8") (pin "3") (pinfunction "INH_3") (pintype "passive"))
    )
    (net (code "62") (name "Net-(U8-IS)") (class "Default")
      (node (ref "C79") (pin "2") (pinfunction "2_2") (pintype "passive"))
      (node (ref "R30") (pin "1") (pinfunction "1_1") (pintype "passive"))
      (node (ref "U8") (pin "6") (pinfunction "IS_6") (pintype "passive"))
    )
    (net (code "63") (name "Net-(U8-SR)") (class "Default")
      (node (ref "C78") (pin "1") (pinfunction "1_1") (pintype "passive"))
      (node (ref "R24") (pin "2") (pinfunction "2_2") (pintype "passive"))
      (node (ref "U8") (pin "5") (pinfunction "SR_5") (pintype "passive"))
    )
    (net (code "64") (name "Net-(U9-IN)") (class "Default")
      (node (ref "R28") (pin "2") (pinfunction "2_2") (pintype "passive"))
      (node (ref "U9") (pin "2") (pinfunction "IN_2") (pintype "passive"))
    )
    (net (code "65") (name "Net-(U9-INH)") (class "Default")
      (node (ref "R25") (pin "2") (pinfunction "2_2") (pintype "passive"))
      (node (ref "U9") (pin "3") (pinfunction "INH_3") (pintype "passive"))
    )
    (net (code "66") (name "Net-(U9-IS)") (class "Default")
      (node (ref "C81") (pin "2") (pinfunction "2_2") (pintype "passive"))
      (node (ref "R43") (pin "1") (pinfunction "1_1") (pintype "passive"))
      (node (ref "U9") (pin "6") (pinfunction "IS_6") (pintype "passive"))
    )
    (net (code "67") (name "Net-(U9-SR)") (class "Default")
      (node (ref "C80") (pin "1") (pinfunction "1_1") (pintype "passive"))
      (node (ref "R31") (pin "2") (pinfunction "2_2") (pintype "passive"))
      (node (ref "U9") (pin "5") (pinfunction "SR_5") (pintype "passive"))
    )
    (net (code "68") (name "Net-(U10-IS)") (class "Default")
      (node (ref "R26") (pin "1") (pinfunction "1_1") (pintype "passive"))
      (node (ref "U10") (pin "4") (pinfunction "IS_4") (pintype "passive"))
    )
    (net (code "69") (name "Net-(U11-IS)") (class "Default")
      (node (ref "R32") (pin "1") (pinfunction "1_1") (pintype "passive"))
      (node (ref "U11") (pin "4") (pinfunction "IS_4") (pintype "passive"))
    )
    (net (code "70") (name "Net-(U12-IN)") (class "Default")
      (node (ref "R36") (pin "2") (pinfunction "2_2") (pintype "passive"))
      (node (ref "U12") (pin "2") (pinfunction "IN_2") (pintype "passive"))
    )
    (net (code "71") (name "Net-(U12-INH)") (class "Default")
      (node (ref "R34") (pin "2") (pinfunction "2_2") (pintype "passive"))
      (node (ref "U12") (pin "3") (pinfunction "INH_3") (pintype "passive"))
    )
    (net (code "72") (name "Net-(U12-IS)") (class "Default")
      (node (ref "C83") (pin "2") (pinfunction "2_2") (pintype "passive"))
      (node (ref "R138") (pin "1") (pinfunction "1_1") (pintype "passive"))
      (node (ref "U12") (pin "6") (pinfunction "IS_6") (pintype "passive"))
    )
    (net (code "73") (name "Net-(U12-SR)") (class "Default")
      (node (ref "C82") (pin "1") (pinfunction "1_1") (pintype "passive"))
      (node (ref "R37") (pin "2") (pinfunction "2_2") (pintype "passive"))
      (node (ref "U12") (pin "5") (pinfunction "SR_5") (pintype "passive"))
    )
    (net (code "74") (name "Net-(U13-IS)") (class "Default")
      (node (ref "R38") (pin "1") (pinfunction "1_1") (pintype "passive"))
      (node (ref "U13") (pin "4") (pinfunction "IS_4") (pintype "passive"))
    )
    (net (code "75") (name "Net-(U14-IN)") (class "Default")
      (node (ref "R42") (pin "2") (pinfunction "2_2") (pintype "passive"))
      (node (ref "U14") (pin "2") (pinfunction "IN_2") (pintype "passive"))
    )
    (net (code "76") (name "Net-(U14-INH)") (class "Default")
      (node (ref "R40") (pin "2") (pinfunction "2_2") (pintype "passive"))
      (node (ref "U14") (pin "3") (pinfunction "INH_3") (pintype "passive"))
    )
    (net (code "77") (name "Net-(U14-IS)") (class "Default")
      (node (ref "C85") (pin "2") (pinfunction "2_2") (pintype "passive"))
      (node (ref "R139") (pin "1") (pinfunction "1_1") (pintype "passive"))
      (node (ref "U14") (pin "6") (pinfunction "IS_6") (pintype "passive"))
    )
    (net (code "78") (name "Net-(U14-SR)") (class "Default")
      (node (ref "C84") (pin "1") (pinfunction "1_1") (pintype "passive"))
      (node (ref "R44") (pin "2") (pinfunction "2_2") (pintype "passive"))
      (node (ref "U14") (pin "5") (pinfunction "SR_5") (pintype "passive"))
    )
    (net (code "80") (name "PD4") (class "Default")
      (node (ref "R21") (pin "1") (pinfunction "1_1") (pintype "passive"))
      (node (ref "R25") (pin "1") (pinfunction "1_1") (pintype "passive"))
    )
    (net (code "81") (name "PG0") (class "Default")
      (node (ref "R23") (pin "1") (pinfunction "1_1") (pintype "passive"))
    )
    (net (code "82") (name "PG1") (class "Default")
      (node (ref "R28") (pin "1") (pinfunction "1_1") (pintype "passive"))
    )
    (net (code "83") (name "PG2") (class "Default")
      (node (ref "R36") (pin "1") (pinfunction "1_1") (pintype "passive"))
    )
    (net (code "84") (name "PG3") (class "Default")
      (node (ref "R42") (pin "1") (pinfunction "1_1") (pintype "passive"))
    )
    (net (code "85") (name "PG4") (class "Default")
      (node (ref "R34") (pin "1") (pinfunction "1_1") (pintype "passive"))
      (node (ref "R40") (pin "1") (pinfunction "1_1") (pintype "passive"))
    )
    (net (code "86") (name "unconnected-(J8-Pad1)") (class "Default")
      (node (ref "J8") (pin "1") (pinfunction "1_1") (pintype "passive+no_connect"))
    )
    (net (code "87") (name "unconnected-(J8-Pad2)") (class "Default")
      (node (ref "J8") (pin "2") (pinfunction "2_2") (pintype "passive+no_connect"))
    )
  )
)
